# V6523_v2.net
KiCad netlist of a schematic drawn in EAGLE
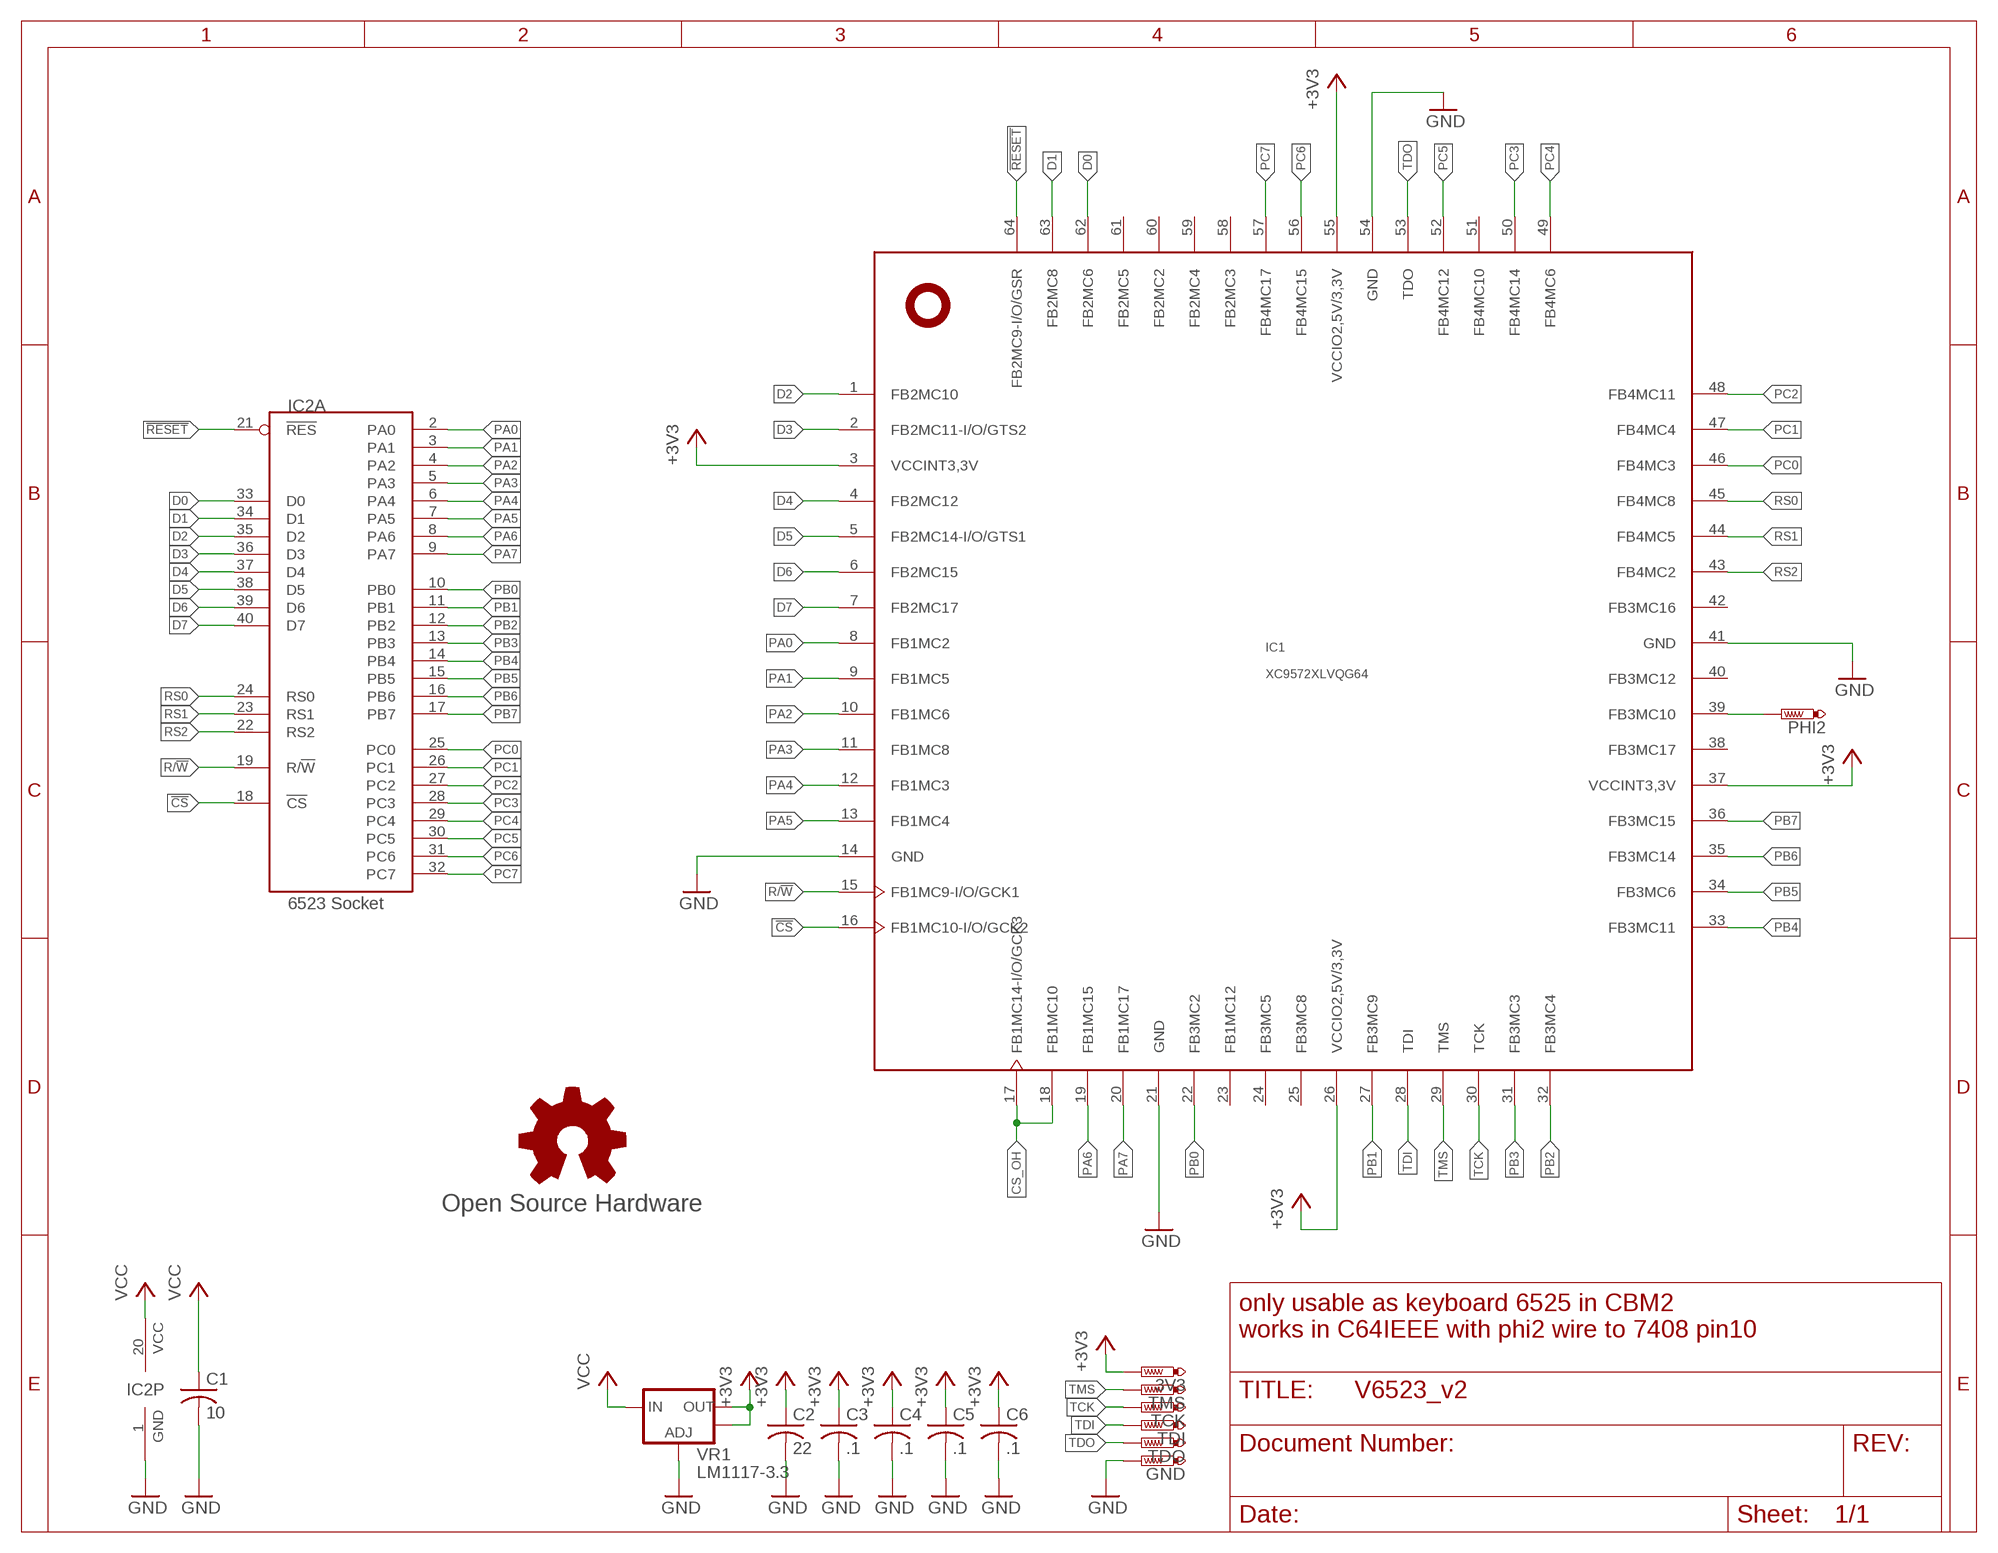
[diagram p0: schematic, sheet 1]

(export (version "E")
  (design (tool "Eeschema 10.0.6"))
  (components
    (comp (ref "3V3")
      (value "PTR1TP08R")
      (footprint "eagle-import:TP08R")
      (libsource (lib "eagle-import") (part "PTR1TP08R"))
    )
    (comp (ref "C1")
      (value "10")
      (footprint "eagle-import:C0805")
      (libsource (lib "eagle-import") (part "C-USC0805"))
    )
    (comp (ref "C2")
      (value "22")
      (footprint "eagle-import:C0805")
      (libsource (lib "eagle-import") (part "C-USC0805"))
    )
    (comp (ref "C3")
      (value ".1")
      (footprint "eagle-import:C0603")
      (libsource (lib "eagle-import") (part "C-USC0603"))
    )
    (comp (ref "C4")
      (value ".1")
      (footprint "eagle-import:C0603")
      (libsource (lib "eagle-import") (part "C-USC0603"))
    )
    (comp (ref "C5")
      (value ".1")
      (footprint "eagle-import:C0603")
      (libsource (lib "eagle-import") (part "C-USC0603"))
    )
    (comp (ref "C6")
      (value ".1")
      (footprint "eagle-import:C0603")
      (libsource (lib "eagle-import") (part "C-USC0603"))
    )
    (comp (ref "GND")
      (value "PTR1TP08R")
      (footprint "eagle-import:TP08R")
      (libsource (lib "eagle-import") (part "PTR1TP08R"))
    )
    (comp (ref "GOLD_ORB_SM1")
      (value "Open Source Hardware")
      (footprint "eagle-import:OSHW_5MM")
      (libsource (lib "eagle-import") (part "OSHWLOGOLOGO5MM"))
    )
    (comp (ref "IC1")
      (value "XC9572XLVQG64")
      (footprint "eagle-import:VQFP64")
      (libsource (lib "eagle-import") (part "XC9572XLVQG64"))
    )
    (comp (ref "IC2")
      (value "6523 Socket")
      (footprint "eagle-import:DIL40-RP-NOFRAME")
      (libsource (lib "eagle-import") (part "6523NOFRAME"))
    )
    (comp (ref "PHI2")
      (value "PTR1TP08R")
      (footprint "eagle-import:TP08R")
      (libsource (lib "eagle-import") (part "PTR1TP08R"))
    )
    (comp (ref "TCK")
      (value "PTR1TP08R")
      (footprint "eagle-import:TP08R")
      (libsource (lib "eagle-import") (part "PTR1TP08R"))
    )
    (comp (ref "TDI")
      (value "PTR1TP08R")
      (footprint "eagle-import:TP08R")
      (libsource (lib "eagle-import") (part "PTR1TP08R"))
    )
    (comp (ref "TDO")
      (value "PTR1TP08R")
      (footprint "eagle-import:TP08R")
      (libsource (lib "eagle-import") (part "PTR1TP08R"))
    )
    (comp (ref "TMS")
      (value "PTR1TP08R")
      (footprint "eagle-import:TP08R")
      (libsource (lib "eagle-import") (part "PTR1TP08R"))
    )
    (comp (ref "VR1")
      (value "LM1117-3.3")
      (footprint "eagle-import:SOT223")
      (libsource (lib "eagle-import") (part "V_REG_LM1117SOT223"))
    )
  )
  (nets
    (net (code "1") (name "+3V3") (class "Default")
      (node (ref "3V3") (pin "TP") (pinfunction "TP_TP") (pintype "input"))
      (node (ref "C2") (pin "1") (pinfunction "1_1") (pintype "passive"))
      (node (ref "C3") (pin "1") (pinfunction "1_1") (pintype "passive"))
      (node (ref "C4") (pin "1") (pinfunction "1_1") (pintype "passive"))
      (node (ref "C5") (pin "1") (pinfunction "1_1") (pintype "passive"))
      (node (ref "C6") (pin "1") (pinfunction "1_1") (pintype "passive"))
      (node (ref "IC1") (pin "26") (pinfunction "VCCIO2,5V/3,3V_26") (pintype "power_in"))
      (node (ref "IC1") (pin "3") (pinfunction "VCCINT3,3V_3") (pintype "power_in"))
      (node (ref "IC1") (pin "37") (pinfunction "VCCINT3,3V_37") (pintype "power_in"))
      (node (ref "IC1") (pin "55") (pinfunction "VCCIO2,5V/3,3V_55") (pintype "power_in"))
      (node (ref "VR1") (pin "2") (pinfunction "OUT_2") (pintype "output"))
      (node (ref "VR1") (pin "4") (pinfunction "OUT_4") (pintype "output"))
    )
    (net (code "2") (name "/R{slash}~{W}") (class "Default")
      (node (ref "IC1") (pin "15") (pinfunction "FB1MC9-I/O/GCK1_15") (pintype "bidirectional"))
      (node (ref "IC2") (pin "19") (pinfunction "R/~{W}_19") (pintype "input"))
    )
    (net (code "3") (name "/~{CS}") (class "Default")
      (node (ref "IC1") (pin "16") (pinfunction "FB1MC10-I/O/GCK2_16") (pintype "bidirectional"))
      (node (ref "IC2") (pin "18") (pinfunction "~{CS}_18") (pintype "input"))
    )
    (net (code "4") (name "/~{RESET}") (class "Default")
      (node (ref "IC1") (pin "64") (pinfunction "FB2MC9-I/O/GSR_64") (pintype "bidirectional"))
      (node (ref "IC2") (pin "21") (pinfunction "~{RES}_21") (pintype "input"))
    )
    (net (code "5") (name "CS_OH") (class "Default")
      (node (ref "IC1") (pin "17") (pinfunction "FB1MC14-I/O/GCK3_17") (pintype "bidirectional"))
      (node (ref "IC1") (pin "18") (pinfunction "FB1MC10_18") (pintype "bidirectional"))
    )
    (net (code "6") (name "D0") (class "Default")
      (node (ref "IC1") (pin "62") (pinfunction "FB2MC6_62") (pintype "bidirectional"))
      (node (ref "IC2") (pin "33") (pinfunction "D0_33") (pintype "bidirectional"))
    )
    (net (code "7") (name "D1") (class "Default")
      (node (ref "IC1") (pin "63") (pinfunction "FB2MC8_63") (pintype "bidirectional"))
      (node (ref "IC2") (pin "34") (pinfunction "D1_34") (pintype "bidirectional"))
    )
    (net (code "8") (name "D2") (class "Default")
      (node (ref "IC1") (pin "1") (pinfunction "FB2MC10_1") (pintype "bidirectional"))
      (node (ref "IC2") (pin "35") (pinfunction "D2_35") (pintype "bidirectional"))
    )
    (net (code "9") (name "D3") (class "Default")
      (node (ref "IC1") (pin "2") (pinfunction "FB2MC11-I/O/GTS2_2") (pintype "bidirectional"))
      (node (ref "IC2") (pin "36") (pinfunction "D3_36") (pintype "bidirectional"))
    )
    (net (code "10") (name "D4") (class "Default")
      (node (ref "IC1") (pin "4") (pinfunction "FB2MC12_4") (pintype "bidirectional"))
      (node (ref "IC2") (pin "37") (pinfunction "D4_37") (pintype "bidirectional"))
    )
    (net (code "11") (name "D5") (class "Default")
      (node (ref "IC1") (pin "5") (pinfunction "FB2MC14-I/O/GTS1_5") (pintype "bidirectional"))
      (node (ref "IC2") (pin "38") (pinfunction "D5_38") (pintype "bidirectional"))
    )
    (net (code "12") (name "D6") (class "Default")
      (node (ref "IC1") (pin "6") (pinfunction "FB2MC15_6") (pintype "bidirectional"))
      (node (ref "IC2") (pin "39") (pinfunction "D6_39") (pintype "bidirectional"))
    )
    (net (code "13") (name "D7") (class "Default")
      (node (ref "IC1") (pin "7") (pinfunction "FB2MC17_7") (pintype "bidirectional"))
      (node (ref "IC2") (pin "40") (pinfunction "D7_40") (pintype "bidirectional"))
    )
    (net (code "14") (name "GND") (class "Default")
      (node (ref "C1") (pin "2") (pinfunction "2_2") (pintype "passive"))
      (node (ref "C2") (pin "2") (pinfunction "2_2") (pintype "passive"))
      (node (ref "C3") (pin "2") (pinfunction "2_2") (pintype "passive"))
      (node (ref "C4") (pin "2") (pinfunction "2_2") (pintype "passive"))
      (node (ref "C5") (pin "2") (pinfunction "2_2") (pintype "passive"))
      (node (ref "C6") (pin "2") (pinfunction "2_2") (pintype "passive"))
      (node (ref "GND") (pin "TP") (pinfunction "TP_TP") (pintype "input"))
      (node (ref "IC1") (pin "14") (pinfunction "GND_14") (pintype "power_in"))
      (node (ref "IC1") (pin "21") (pinfunction "GND_21") (pintype "power_in"))
      (node (ref "IC1") (pin "41") (pinfunction "GND_41") (pintype "power_in"))
      (node (ref "IC1") (pin "54") (pinfunction "GND_54") (pintype "power_in"))
      (node (ref "IC2") (pin "1") (pinfunction "GND_1") (pintype "power_in"))
      (node (ref "VR1") (pin "1") (pinfunction "ADJ_1") (pintype "input"))
    )
    (net (code "15") (name "Net-(IC1-FB3MC10)") (class "Default")
      (node (ref "IC1") (pin "39") (pinfunction "FB3MC10_39") (pintype "bidirectional"))
      (node (ref "PHI2") (pin "TP") (pinfunction "TP_TP") (pintype "input"))
    )
    (net (code "16") (name "PA0") (class "Default")
      (node (ref "IC1") (pin "8") (pinfunction "FB1MC2_8") (pintype "bidirectional"))
      (node (ref "IC2") (pin "2") (pinfunction "PA0_2") (pintype "bidirectional"))
    )
    (net (code "17") (name "PA1") (class "Default")
      (node (ref "IC1") (pin "9") (pinfunction "FB1MC5_9") (pintype "bidirectional"))
      (node (ref "IC2") (pin "3") (pinfunction "PA1_3") (pintype "bidirectional"))
    )
    (net (code "18") (name "PA2") (class "Default")
      (node (ref "IC1") (pin "10") (pinfunction "FB1MC6_10") (pintype "bidirectional"))
      (node (ref "IC2") (pin "4") (pinfunction "PA2_4") (pintype "bidirectional"))
    )
    (net (code "19") (name "PA3") (class "Default")
      (node (ref "IC1") (pin "11") (pinfunction "FB1MC8_11") (pintype "bidirectional"))
      (node (ref "IC2") (pin "5") (pinfunction "PA3_5") (pintype "bidirectional"))
    )
    (net (code "20") (name "PA4") (class "Default")
      (node (ref "IC1") (pin "12") (pinfunction "FB1MC3_12") (pintype "bidirectional"))
      (node (ref "IC2") (pin "6") (pinfunction "PA4_6") (pintype "bidirectional"))
    )
    (net (code "21") (name "PA5") (class "Default")
      (node (ref "IC1") (pin "13") (pinfunction "FB1MC4_13") (pintype "bidirectional"))
      (node (ref "IC2") (pin "7") (pinfunction "PA5_7") (pintype "bidirectional"))
    )
    (net (code "22") (name "PA6") (class "Default")
      (node (ref "IC1") (pin "19") (pinfunction "FB1MC15_19") (pintype "bidirectional"))
      (node (ref "IC2") (pin "8") (pinfunction "PA6_8") (pintype "bidirectional"))
    )
    (net (code "23") (name "PA7") (class "Default")
      (node (ref "IC1") (pin "20") (pinfunction "FB1MC17_20") (pintype "bidirectional"))
      (node (ref "IC2") (pin "9") (pinfunction "PA7_9") (pintype "bidirectional"))
    )
    (net (code "24") (name "PB0") (class "Default")
      (node (ref "IC1") (pin "22") (pinfunction "FB3MC2_22") (pintype "bidirectional"))
      (node (ref "IC2") (pin "10") (pinfunction "PB0_10") (pintype "bidirectional"))
    )
    (net (code "25") (name "PB1") (class "Default")
      (node (ref "IC1") (pin "27") (pinfunction "FB3MC9_27") (pintype "bidirectional"))
      (node (ref "IC2") (pin "11") (pinfunction "PB1_11") (pintype "bidirectional"))
    )
    (net (code "26") (name "PB2") (class "Default")
      (node (ref "IC1") (pin "32") (pinfunction "FB3MC4_32") (pintype "bidirectional"))
      (node (ref "IC2") (pin "12") (pinfunction "PB2_12") (pintype "bidirectional"))
    )
    (net (code "27") (name "PB3") (class "Default")
      (node (ref "IC1") (pin "31") (pinfunction "FB3MC3_31") (pintype "bidirectional"))
      (node (ref "IC2") (pin "13") (pinfunction "PB3_13") (pintype "bidirectional"))
    )
    (net (code "28") (name "PB4") (class "Default")
      (node (ref "IC1") (pin "33") (pinfunction "FB3MC11_33") (pintype "bidirectional"))
      (node (ref "IC2") (pin "14") (pinfunction "PB4_14") (pintype "bidirectional"))
    )
    (net (code "29") (name "PB5") (class "Default")
      (node (ref "IC1") (pin "34") (pinfunction "FB3MC6_34") (pintype "bidirectional"))
      (node (ref "IC2") (pin "15") (pinfunction "PB5_15") (pintype "bidirectional"))
    )
    (net (code "30") (name "PB6") (class "Default")
      (node (ref "IC1") (pin "35") (pinfunction "FB3MC14_35") (pintype "bidirectional"))
      (node (ref "IC2") (pin "16") (pinfunction "PB6_16") (pintype "bidirectional"))
    )
    (net (code "31") (name "PB7") (class "Default")
      (node (ref "IC1") (pin "36") (pinfunction "FB3MC15_36") (pintype "bidirectional"))
      (node (ref "IC2") (pin "17") (pinfunction "PB7_17") (pintype "bidirectional"))
    )
    (net (code "32") (name "PC0") (class "Default")
      (node (ref "IC1") (pin "46") (pinfunction "FB4MC3_46") (pintype "bidirectional"))
      (node (ref "IC2") (pin "25") (pinfunction "PC0_25") (pintype "bidirectional"))
    )
    (net (code "33") (name "PC1") (class "Default")
      (node (ref "IC1") (pin "47") (pinfunction "FB4MC4_47") (pintype "bidirectional"))
      (node (ref "IC2") (pin "26") (pinfunction "PC1_26") (pintype "bidirectional"))
    )
    (net (code "34") (name "PC2") (class "Default")
      (node (ref "IC1") (pin "48") (pinfunction "FB4MC11_48") (pintype "bidirectional"))
      (node (ref "IC2") (pin "27") (pinfunction "PC2_27") (pintype "bidirectional"))
    )
    (net (code "35") (name "PC3") (class "Default")
      (node (ref "IC1") (pin "50") (pinfunction "FB4MC14_50") (pintype "bidirectional"))
      (node (ref "IC2") (pin "28") (pinfunction "PC3_28") (pintype "bidirectional"))
    )
    (net (code "36") (name "PC4") (class "Default")
      (node (ref "IC1") (pin "49") (pinfunction "FB4MC6_49") (pintype "bidirectional"))
      (node (ref "IC2") (pin "29") (pinfunction "PC4_29") (pintype "bidirectional"))
    )
    (net (code "37") (name "PC5") (class "Default")
      (node (ref "IC1") (pin "52") (pinfunction "FB4MC12_52") (pintype "bidirectional"))
      (node (ref "IC2") (pin "30") (pinfunction "PC5_30") (pintype "bidirectional"))
    )
    (net (code "38") (name "PC6") (class "Default")
      (node (ref "IC1") (pin "56") (pinfunction "FB4MC15_56") (pintype "bidirectional"))
      (node (ref "IC2") (pin "31") (pinfunction "PC6_31") (pintype "bidirectional"))
    )
    (net (code "39") (name "PC7") (class "Default")
      (node (ref "IC1") (pin "57") (pinfunction "FB4MC17_57") (pintype "bidirectional"))
      (node (ref "IC2") (pin "32") (pinfunction "PC7_32") (pintype "bidirectional"))
    )
    (net (code "40") (name "RS0") (class "Default")
      (node (ref "IC1") (pin "45") (pinfunction "FB4MC8_45") (pintype "bidirectional"))
      (node (ref "IC2") (pin "24") (pinfunction "RS0_24") (pintype "input"))
    )
    (net (code "41") (name "RS1") (class "Default")
      (node (ref "IC1") (pin "44") (pinfunction "FB4MC5_44") (pintype "bidirectional"))
      (node (ref "IC2") (pin "23") (pinfunction "RS1_23") (pintype "input"))
    )
    (net (code "42") (name "RS2") (class "Default")
      (node (ref "IC1") (pin "43") (pinfunction "FB4MC2_43") (pintype "bidirectional"))
      (node (ref "IC2") (pin "22") (pinfunction "RS2_22") (pintype "input"))
    )
    (net (code "43") (name "TCK") (class "Default")
      (node (ref "IC1") (pin "30") (pinfunction "TCK_30") (pintype "bidirectional"))
      (node (ref "TCK") (pin "TP") (pinfunction "TP_TP") (pintype "input"))
    )
    (net (code "44") (name "TDI") (class "Default")
      (node (ref "IC1") (pin "28") (pinfunction "TDI_28") (pintype "bidirectional"))
      (node (ref "TDI") (pin "TP") (pinfunction "TP_TP") (pintype "input"))
    )
    (net (code "45") (name "TDO") (class "Default")
      (node (ref "IC1") (pin "53") (pinfunction "TDO_53") (pintype "bidirectional"))
      (node (ref "TDO") (pin "TP") (pinfunction "TP_TP") (pintype "input"))
    )
    (net (code "46") (name "TMS") (class "Default")
      (node (ref "IC1") (pin "29") (pinfunction "TMS_29") (pintype "bidirectional"))
      (node (ref "TMS") (pin "TP") (pinfunction "TP_TP") (pintype "input"))
    )
    (net (code "47") (name "VCC") (class "Default")
      (node (ref "C1") (pin "1") (pinfunction "1_1") (pintype "passive"))
      (node (ref "IC2") (pin "20") (pinfunction "VCC_20") (pintype "power_in"))
      (node (ref "VR1") (pin "3") (pinfunction "IN_3") (pintype "input"))
    )
    (net (code "48") (name "unconnected-(IC1-FB1MC12-Pad23)") (class "Default")
      (node (ref "IC1") (pin "23") (pinfunction "FB1MC12_23") (pintype "bidirectional"))
    )
    (net (code "49") (name "unconnected-(IC1-FB2MC2-Pad60)") (class "Default")
      (node (ref "IC1") (pin "60") (pinfunction "FB2MC2_60") (pintype "bidirectional"))
    )
    (net (code "50") (name "unconnected-(IC1-FB2MC3-Pad58)") (class "Default")
      (node (ref "IC1") (pin "58") (pinfunction "FB2MC3_58") (pintype "bidirectional"))
    )
    (net (code "51") (name "unconnected-(IC1-FB2MC4-Pad59)") (class "Default")
      (node (ref "IC1") (pin "59") (pinfunction "FB2MC4_59") (pintype "bidirectional"))
    )
    (net (code "52") (name "unconnected-(IC1-FB2MC5-Pad61)") (class "Default")
      (node (ref "IC1") (pin "61") (pinfunction "FB2MC5_61") (pintype "bidirectional"))
    )
    (net (code "53") (name "unconnected-(IC1-FB3MC5-Pad24)") (class "Default")
      (node (ref "IC1") (pin "24") (pinfunction "FB3MC5_24") (pintype "bidirectional"))
    )
    (net (code "54") (name "unconnected-(IC1-FB3MC8-Pad25)") (class "Default")
      (node (ref "IC1") (pin "25") (pinfunction "FB3MC8_25") (pintype "bidirectional"))
    )
    (net (code "55") (name "unconnected-(IC1-FB3MC12-Pad40)") (class "Default")
      (node (ref "IC1") (pin "40") (pinfunction "FB3MC12_40") (pintype "bidirectional"))
    )
    (net (code "56") (name "unconnected-(IC1-FB3MC16-Pad42)") (class "Default")
      (node (ref "IC1") (pin "42") (pinfunction "FB3MC16_42") (pintype "bidirectional"))
    )
    (net (code "57") (name "unconnected-(IC1-FB3MC17-Pad38)") (class "Default")
      (node (ref "IC1") (pin "38") (pinfunction "FB3MC17_38") (pintype "bidirectional"))
    )
    (net (code "58") (name "unconnected-(IC1-FB4MC10-Pad51)") (class "Default")
      (node (ref "IC1") (pin "51") (pinfunction "FB4MC10_51") (pintype "bidirectional"))
    )
  )
)
